# lamp.net
KiCad netlist of a schematic drawn in EAGLE
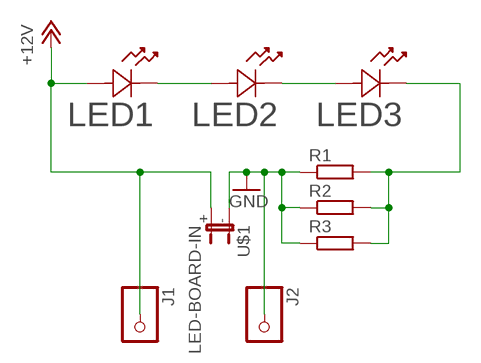
[diagram p0: schematic, sheet 1]

(export (version "E")
  (design (tool "Eeschema 10.0.6"))
  (components
    (comp (ref "J1")
      (value "LARGE-SOLDERPAD")
      (footprint "eagle-import:LARGE-SOLDERPAD")
      (libsource (lib "eagle-import") (part "LARGE-SOLDERPAD"))
    )
    (comp (ref "J2")
      (value "LARGE-SOLDERPAD")
      (footprint "eagle-import:LARGE-SOLDERPAD")
      (libsource (lib "eagle-import") (part "LARGE-SOLDERPAD"))
    )
    (comp (ref "LED1")
      (value "LED-2835LED_J2835_CRW-M")
      (footprint "eagle-import:LED_J2835_CRW-M")
      (fields
        (field (name "MANUFACTURER_PART_NUMBER") "JB2835AWT-W-U30GA0000-N0000001")
        (field (name "COPYRIGHT") "Copyright (C) 2024 Ultra Librarian. All rights reserved.")
      )
      (libsource (lib "eagle-import") (part "LED-2835LED_J2835_CRW-M"))
    )
    (comp (ref "LED2")
      (value "LED-2835LED_J2835_CRW-M")
      (footprint "eagle-import:LED_J2835_CRW-M")
      (fields
        (field (name "MANUFACTURER_PART_NUMBER") "JB2835AWT-W-U30GA0000-N0000001")
        (field (name "COPYRIGHT") "Copyright (C) 2024 Ultra Librarian. All rights reserved.")
      )
      (libsource (lib "eagle-import") (part "LED-2835LED_J2835_CRW-M"))
    )
    (comp (ref "LED3")
      (value "LED-2835LED_J2835_CRW-M")
      (footprint "eagle-import:LED_J2835_CRW-M")
      (fields
        (field (name "MANUFACTURER_PART_NUMBER") "JB2835AWT-W-U30GA0000-N0000001")
        (field (name "COPYRIGHT") "Copyright (C) 2024 Ultra Librarian. All rights reserved.")
      )
      (libsource (lib "eagle-import") (part "LED-2835LED_J2835_CRW-M"))
    )
    (comp (ref "R1")
      (value "R-EU_R0805")
      (footprint "eagle-import:R0805")
      (libsource (lib "eagle-import") (part "R-EU_R0805"))
    )
    (comp (ref "R2")
      (value "R-EU_R0805")
      (footprint "eagle-import:R0805")
      (libsource (lib "eagle-import") (part "R-EU_R0805"))
    )
    (comp (ref "R3")
      (value "R-EU_R0805")
      (footprint "eagle-import:R0805")
      (libsource (lib "eagle-import") (part "R-EU_R0805"))
    )
    (comp (ref "U$1")
      (value "LED-BOARD-IN")
      (footprint "eagle-import:LED-BOARD-IN")
      (libsource (lib "eagle-import") (part "LED-BOARD-IN"))
    )
  )
  (nets
    (net (code "1") (name "+12V") (class "Default")
      (node (ref "J1") (pin "P$1") (pinfunction "1_P$1") (pintype "passive"))
      (node (ref "LED1") (pin "2") (pinfunction "2_2") (pintype "passive"))
      (node (ref "U$1") (pin "+") (pinfunction "2_+") (pintype "passive"))
    )
    (net (code "2") (name "GND") (class "Default")
      (node (ref "J2") (pin "P$1") (pinfunction "1_P$1") (pintype "passive"))
      (node (ref "R1") (pin "1") (pinfunction "1_1") (pintype "passive"))
      (node (ref "R2") (pin "1") (pinfunction "1_1") (pintype "passive"))
      (node (ref "R3") (pin "1") (pinfunction "1_1") (pintype "passive"))
      (node (ref "U$1") (pin "-") (pinfunction "1_-") (pintype "passive"))
    )
    (net (code "3") (name "Net-(LED1-Pad1)") (class "Default")
      (node (ref "LED1") (pin "1") (pinfunction "1_1") (pintype "passive"))
      (node (ref "LED2") (pin "2") (pinfunction "2_2") (pintype "passive"))
    )
    (net (code "4") (name "Net-(LED2-Pad1)") (class "Default")
      (node (ref "LED2") (pin "1") (pinfunction "1_1") (pintype "passive"))
      (node (ref "LED3") (pin "2") (pinfunction "2_2") (pintype "passive"))
    )
    (net (code "5") (name "Net-(LED3-Pad1)") (class "Default")
      (node (ref "LED3") (pin "1") (pinfunction "1_1") (pintype "passive"))
      (node (ref "R1") (pin "2") (pinfunction "2_2") (pintype "passive"))
      (node (ref "R2") (pin "2") (pinfunction "2_2") (pintype "passive"))
      (node (ref "R3") (pin "2") (pinfunction "2_2") (pintype "passive"))
    )
  )
)
